# tricolormini.net
KiCad netlist of a schematic drawn in EAGLE
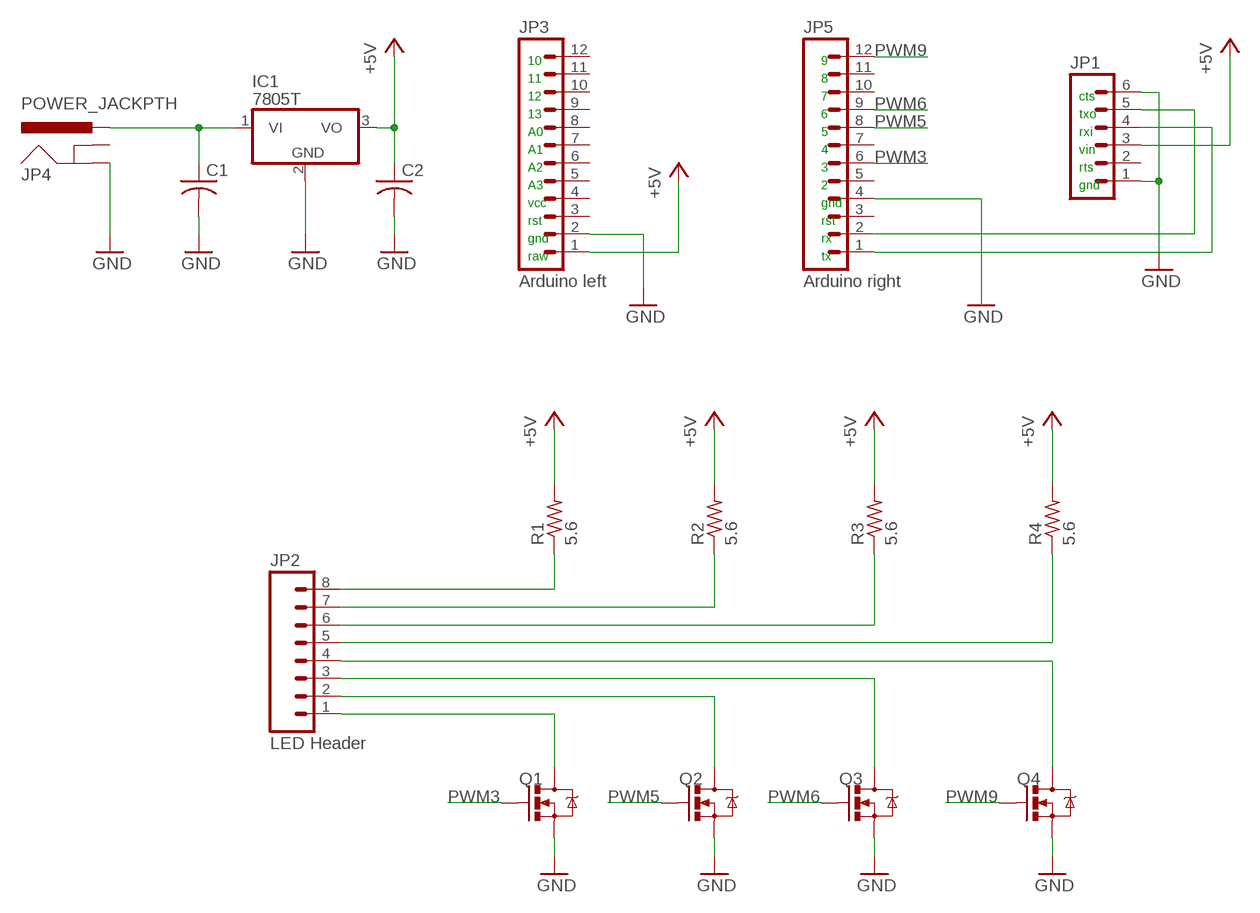
[diagram p0: schematic, sheet 1]

(export (version "E")
  (design (tool "Eeschema 10.0.6"))
  (components
    (comp (ref "C1")
      (value "C-USC1206")
      (footprint "eagle-import:C1206")
      (libsource (lib "eagle-import") (part "C-USC1206"))
    )
    (comp (ref "C2")
      (value "C-USC1206")
      (footprint "eagle-import:C1206")
      (libsource (lib "eagle-import") (part "C-USC1206"))
    )
    (comp (ref "IC1")
      (value "7805T")
      (footprint "eagle-import:TO220H")
      (libsource (lib "eagle-import") (part "78T05"))
    )
    (comp (ref "JP1")
      (value "M06SILK_FEMALE_PTH")
      (footprint "eagle-import:1X06")
      (libsource (lib "eagle-import") (part "M06SILK_FEMALE_PTH"))
    )
    (comp (ref "JP2")
      (value "LED Header")
      (footprint "eagle-import:1X08_ROUND")
      (libsource (lib "eagle-import") (part "M08"))
    )
    (comp (ref "JP3")
      (value "Arduino left")
      (footprint "eagle-import:1X12")
      (libsource (lib "eagle-import") (part "M12PTH"))
    )
    (comp (ref "JP4")
      (value "POWER_JACKPTH")
      (footprint "eagle-import:POWER_JACK_PTH")
      (libsource (lib "eagle-import") (part "POWER_JACKPTH"))
    )
    (comp (ref "JP5")
      (value "Arduino right")
      (footprint "eagle-import:1X12")
      (libsource (lib "eagle-import") (part "M12PTH"))
    )
    (comp (ref "Q1")
      (value "MOSFET-NCHANNELAO3404A")
      (footprint "eagle-import:SOT23-3")
      (libsource (lib "eagle-import") (part "MOSFET-NCHANNELAO3404A"))
    )
    (comp (ref "Q2")
      (value "MOSFET-NCHANNELAO3404A")
      (footprint "eagle-import:SOT23-3")
      (libsource (lib "eagle-import") (part "MOSFET-NCHANNELAO3404A"))
    )
    (comp (ref "Q3")
      (value "MOSFET-NCHANNELAO3404A")
      (footprint "eagle-import:SOT23-3")
      (libsource (lib "eagle-import") (part "MOSFET-NCHANNELAO3404A"))
    )
    (comp (ref "Q4")
      (value "MOSFET-NCHANNELAO3404A")
      (footprint "eagle-import:SOT23-3")
      (libsource (lib "eagle-import") (part "MOSFET-NCHANNELAO3404A"))
    )
    (comp (ref "R1")
      (value "5.6")
      (footprint "eagle-import:0207_10")
      (libsource (lib "eagle-import") (part "R-US_0207/10"))
    )
    (comp (ref "R2")
      (value "5.6")
      (footprint "eagle-import:0207_10")
      (libsource (lib "eagle-import") (part "R-US_0207/10"))
    )
    (comp (ref "R3")
      (value "5.6")
      (footprint "eagle-import:0207_10")
      (libsource (lib "eagle-import") (part "R-US_0207/10"))
    )
    (comp (ref "R4")
      (value "5.6")
      (footprint "eagle-import:0207_10")
      (libsource (lib "eagle-import") (part "R-US_0207/10"))
    )
  )
  (nets
    (net (code "1") (name "+5V") (class "Default")
      (node (ref "C2") (pin "1") (pinfunction "1_1") (pintype "passive"))
      (node (ref "IC1") (pin "3") (pinfunction "VO_3") (pintype "passive"))
      (node (ref "JP1") (pin "3") (pinfunction "3_3") (pintype "passive"))
      (node (ref "JP3") (pin "1") (pinfunction "1_1") (pintype "passive"))
      (node (ref "R1") (pin "2") (pinfunction "2_2") (pintype "passive"))
      (node (ref "R2") (pin "2") (pinfunction "2_2") (pintype "passive"))
      (node (ref "R3") (pin "2") (pinfunction "2_2") (pintype "passive"))
      (node (ref "R4") (pin "2") (pinfunction "2_2") (pintype "passive"))
    )
    (net (code "2") (name "/PWM3") (class "Default")
      (node (ref "JP5") (pin "6") (pinfunction "6_6") (pintype "passive"))
      (node (ref "Q1") (pin "1") (pinfunction "G_1") (pintype "passive"))
    )
    (net (code "3") (name "/PWM5") (class "Default")
      (node (ref "JP5") (pin "8") (pinfunction "8_8") (pintype "passive"))
      (node (ref "Q2") (pin "1") (pinfunction "G_1") (pintype "passive"))
    )
    (net (code "4") (name "/PWM6") (class "Default")
      (node (ref "JP5") (pin "9") (pinfunction "9_9") (pintype "passive"))
      (node (ref "Q3") (pin "1") (pinfunction "G_1") (pintype "passive"))
    )
    (net (code "5") (name "/PWM9") (class "Default")
      (node (ref "JP5") (pin "12") (pinfunction "12_12") (pintype "passive"))
      (node (ref "Q4") (pin "1") (pinfunction "G_1") (pintype "passive"))
    )
    (net (code "6") (name "GND") (class "Default")
      (node (ref "C1") (pin "2") (pinfunction "2_2") (pintype "passive"))
      (node (ref "C2") (pin "2") (pinfunction "2_2") (pintype "passive"))
      (node (ref "IC1") (pin "2") (pinfunction "GND_2") (pintype "passive"))
      (node (ref "JP1") (pin "1") (pinfunction "1_1") (pintype "passive"))
      (node (ref "JP1") (pin "6") (pinfunction "6_6") (pintype "passive"))
      (node (ref "JP3") (pin "2") (pinfunction "2_2") (pintype "passive"))
      (node (ref "JP4") (pin "GND") (pinfunction "GND_GND") (pintype "bidirectional"))
      (node (ref "JP5") (pin "4") (pinfunction "4_4") (pintype "passive"))
      (node (ref "Q1") (pin "2") (pinfunction "S_2") (pintype "passive"))
      (node (ref "Q2") (pin "2") (pinfunction "S_2") (pintype "passive"))
      (node (ref "Q3") (pin "2") (pinfunction "S_2") (pintype "passive"))
      (node (ref "Q4") (pin "2") (pinfunction "S_2") (pintype "passive"))
    )
    (net (code "7") (name "Net-(IC1-VI)") (class "Default")
      (node (ref "C1") (pin "1") (pinfunction "1_1") (pintype "passive"))
      (node (ref "IC1") (pin "1") (pinfunction "VI_1") (pintype "input"))
      (node (ref "JP4") (pin "PWR") (pinfunction "PWR_PWR") (pintype "bidirectional"))
    )
    (net (code "8") (name "Net-(JP1-Pad4)") (class "Default")
      (node (ref "JP1") (pin "4") (pinfunction "4_4") (pintype "passive"))
      (node (ref "JP5") (pin "1") (pinfunction "1_1") (pintype "passive"))
    )
    (net (code "9") (name "Net-(JP1-Pad5)") (class "Default")
      (node (ref "JP1") (pin "5") (pinfunction "5_5") (pintype "passive"))
      (node (ref "JP5") (pin "2") (pinfunction "2_2") (pintype "passive"))
    )
    (net (code "10") (name "Net-(JP2-Pad5)") (class "Default")
      (node (ref "JP2") (pin "5") (pinfunction "5_5") (pintype "passive"))
      (node (ref "R4") (pin "1") (pinfunction "1_1") (pintype "passive"))
    )
    (net (code "11") (name "Net-(JP2-Pad6)") (class "Default")
      (node (ref "JP2") (pin "6") (pinfunction "6_6") (pintype "passive"))
      (node (ref "R3") (pin "1") (pinfunction "1_1") (pintype "passive"))
    )
    (net (code "12") (name "Net-(JP2-Pad7)") (class "Default")
      (node (ref "JP2") (pin "7") (pinfunction "7_7") (pintype "passive"))
      (node (ref "R2") (pin "1") (pinfunction "1_1") (pintype "passive"))
    )
    (net (code "13") (name "Net-(JP2-Pad8)") (class "Default")
      (node (ref "JP2") (pin "8") (pinfunction "8_8") (pintype "passive"))
      (node (ref "R1") (pin "1") (pinfunction "1_1") (pintype "passive"))
    )
    (net (code "14") (name "Net-(Q1-D)") (class "Default")
      (node (ref "JP2") (pin "1") (pinfunction "1_1") (pintype "passive"))
      (node (ref "Q1") (pin "3") (pinfunction "D_3") (pintype "passive"))
    )
    (net (code "15") (name "Net-(Q2-D)") (class "Default")
      (node (ref "JP2") (pin "2") (pinfunction "2_2") (pintype "passive"))
      (node (ref "Q2") (pin "3") (pinfunction "D_3") (pintype "passive"))
    )
    (net (code "16") (name "Net-(Q3-D)") (class "Default")
      (node (ref "JP2") (pin "3") (pinfunction "3_3") (pintype "passive"))
      (node (ref "Q3") (pin "3") (pinfunction "D_3") (pintype "passive"))
    )
    (net (code "17") (name "Net-(Q4-D)") (class "Default")
      (node (ref "JP2") (pin "4") (pinfunction "4_4") (pintype "passive"))
      (node (ref "Q4") (pin "3") (pinfunction "D_3") (pintype "passive"))
    )
    (net (code "18") (name "unconnected-(JP1-Pad2)") (class "Default")
      (node (ref "JP1") (pin "2") (pinfunction "2_2") (pintype "passive"))
    )
    (net (code "19") (name "unconnected-(JP3-Pad3)") (class "Default")
      (node (ref "JP3") (pin "3") (pinfunction "3_3") (pintype "passive"))
    )
    (net (code "20") (name "unconnected-(JP3-Pad4)") (class "Default")
      (node (ref "JP3") (pin "4") (pinfunction "4_4") (pintype "passive"))
    )
    (net (code "21") (name "unconnected-(JP3-Pad5)") (class "Default")
      (node (ref "JP3") (pin "5") (pinfunction "5_5") (pintype "passive"))
    )
    (net (code "22") (name "unconnected-(JP3-Pad6)") (class "Default")
      (node (ref "JP3") (pin "6") (pinfunction "6_6") (pintype "passive"))
    )
    (net (code "23") (name "unconnected-(JP3-Pad7)") (class "Default")
      (node (ref "JP3") (pin "7") (pinfunction "7_7") (pintype "passive"))
    )
    (net (code "24") (name "unconnected-(JP3-Pad8)") (class "Default")
      (node (ref "JP3") (pin "8") (pinfunction "8_8") (pintype "passive"))
    )
    (net (code "25") (name "unconnected-(JP3-Pad9)") (class "Default")
      (node (ref "JP3") (pin "9") (pinfunction "9_9") (pintype "passive"))
    )
    (net (code "26") (name "unconnected-(JP3-Pad10)") (class "Default")
      (node (ref "JP3") (pin "10") (pinfunction "10_10") (pintype "passive"))
    )
    (net (code "27") (name "unconnected-(JP3-Pad11)") (class "Default")
      (node (ref "JP3") (pin "11") (pinfunction "11_11") (pintype "passive"))
    )
    (net (code "28") (name "unconnected-(JP3-Pad12)") (class "Default")
      (node (ref "JP3") (pin "12") (pinfunction "12_12") (pintype "passive"))
    )
    (net (code "29") (name "unconnected-(JP4-PadGNDBREAK)") (class "Default")
      (node (ref "JP4") (pin "GNDBREAK") (pinfunction "GNDBREAK_GNDBREAK") (pintype "bidirectional"))
    )
    (net (code "30") (name "unconnected-(JP5-Pad3)") (class "Default")
      (node (ref "JP5") (pin "3") (pinfunction "3_3") (pintype "passive"))
    )
    (net (code "31") (name "unconnected-(JP5-Pad5)") (class "Default")
      (node (ref "JP5") (pin "5") (pinfunction "5_5") (pintype "passive"))
    )
    (net (code "32") (name "unconnected-(JP5-Pad7)") (class "Default")
      (node (ref "JP5") (pin "7") (pinfunction "7_7") (pintype "passive"))
    )
    (net (code "33") (name "unconnected-(JP5-Pad10)") (class "Default")
      (node (ref "JP5") (pin "10") (pinfunction "10_10") (pintype "passive"))
    )
    (net (code "34") (name "unconnected-(JP5-Pad11)") (class "Default")
      (node (ref "JP5") (pin "11") (pinfunction "11_11") (pintype "passive"))
    )
  )
)
